# team4-selo-atmega32u4.net
KiCad netlist of a schematic drawn in EAGLE
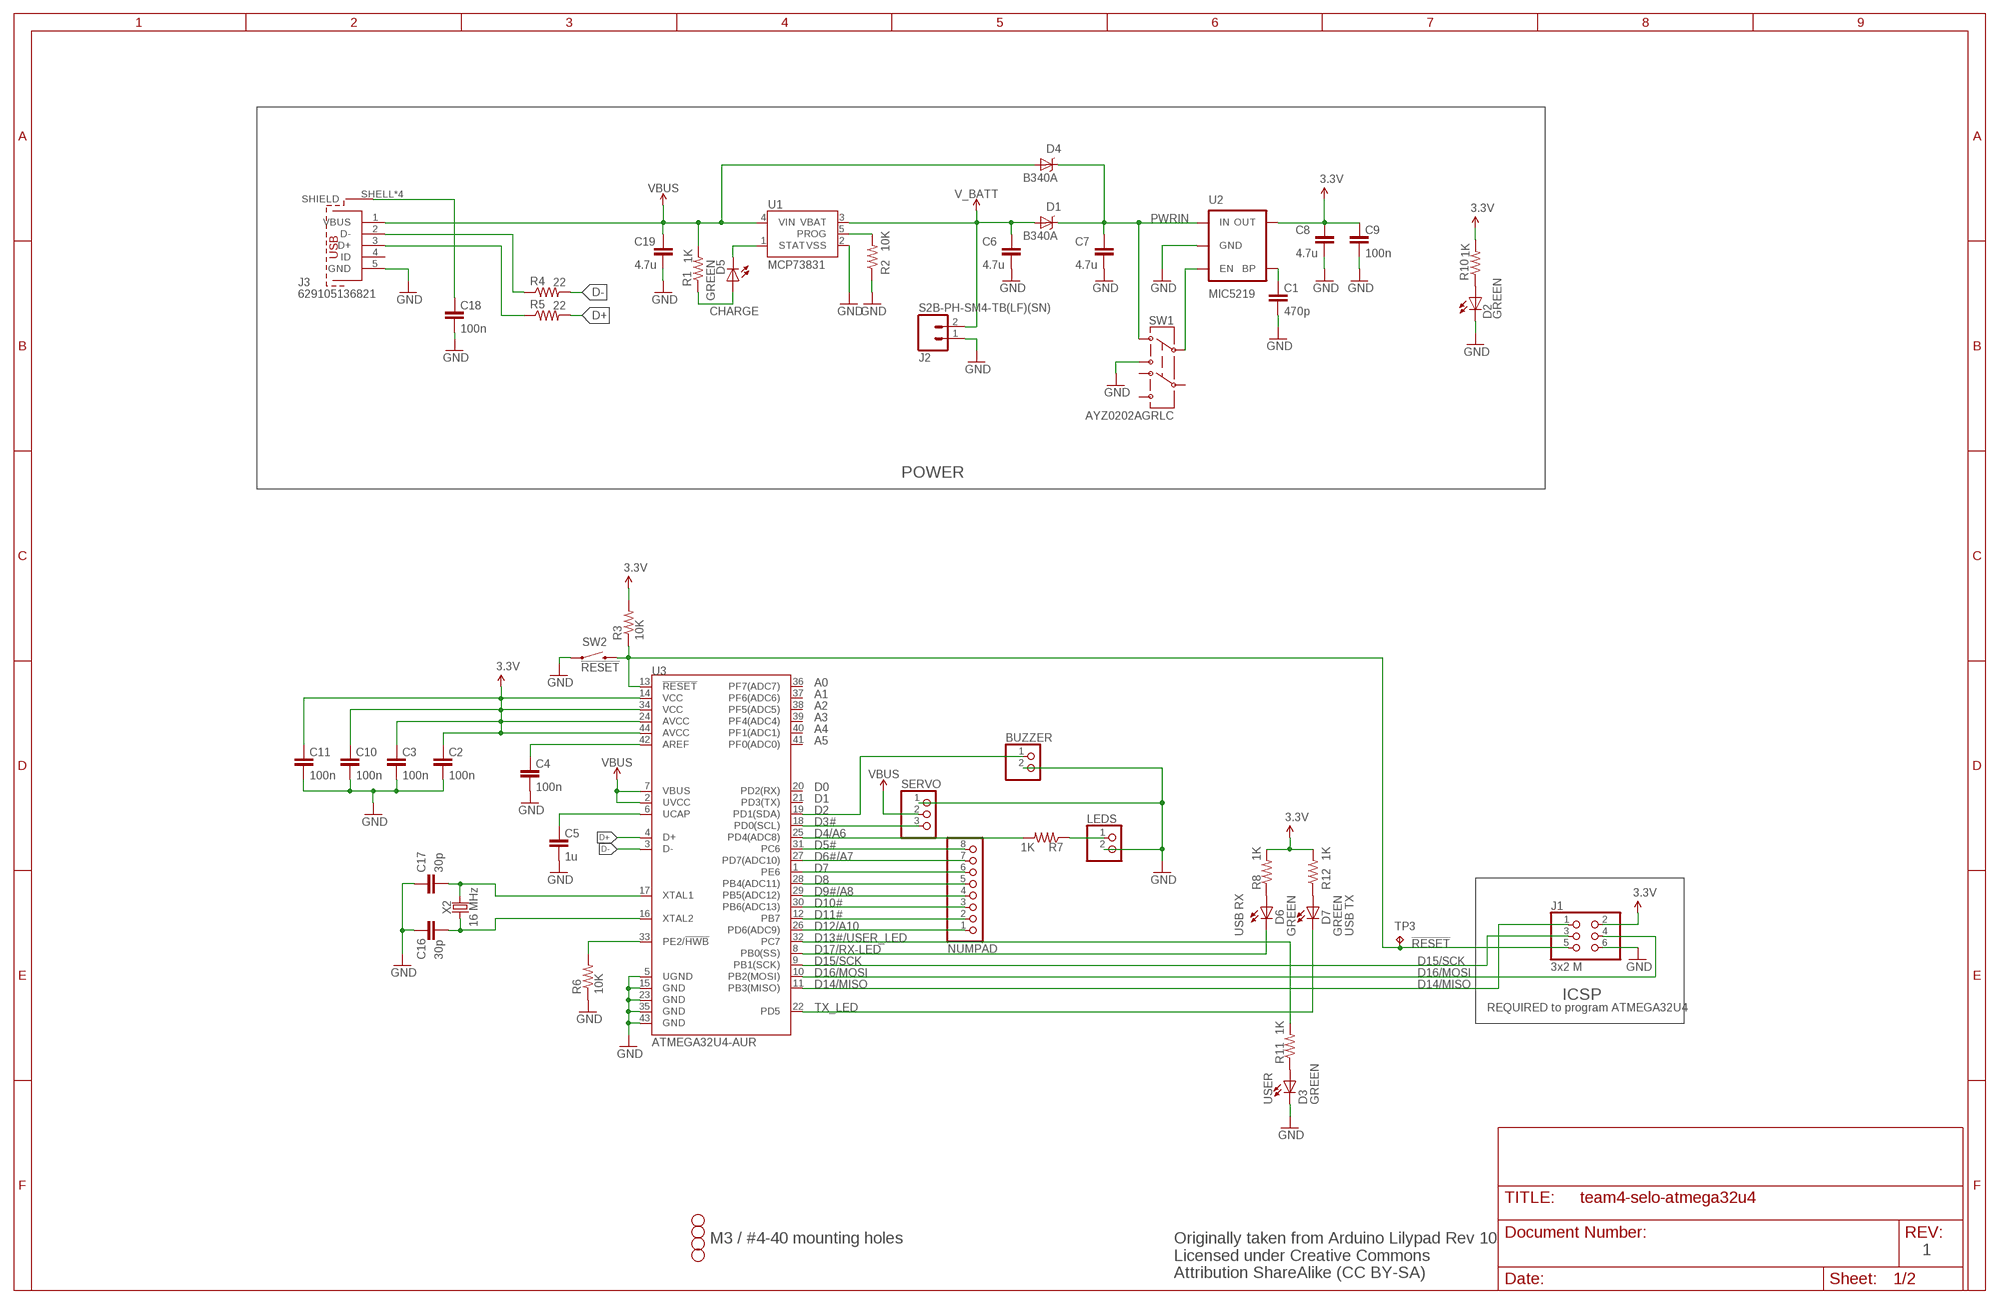
[diagram p0: schematic, sheet 1]

(export (version "E")
  (design (tool "Eeschema 10.0.6"))
  (components
    (comp (ref "BUZZER")
      (value "PINHD-1X2")
      (footprint "eagle-import:1X02")
      (libsource (lib "eagle-import") (part "PINHD-1X2"))
    )
    (comp (ref "C1")
      (value "470p")
      (footprint "eagle-import:C0805K")
      (fields (field (name "MFR") "Samsung") (field (name "MPN") "CL21B471KBANNNC"))
      (libsource (lib "eagle-import") (part "C-EUC0805K"))
    )
    (comp (ref "C2")
      (value "100n")
      (footprint "eagle-import:C0805K")
      (fields (field (name "MFR") "Samsung") (field (name "MPN") "CL21B104KBCNNNC"))
      (libsource (lib "eagle-import") (part "C-EUC0805K"))
    )
    (comp (ref "C3")
      (value "100n")
      (footprint "eagle-import:C0805K")
      (fields (field (name "MFR") "Samsung") (field (name "MPN") "CL21B104KBCNNNC"))
      (libsource (lib "eagle-import") (part "C-EUC0805K"))
    )
    (comp (ref "C4")
      (value "100n")
      (footprint "eagle-import:C0805K")
      (fields (field (name "MFR") "Samsung") (field (name "MPN") "CL21B104KBCNNNC"))
      (libsource (lib "eagle-import") (part "C-EUC0805K"))
    )
    (comp (ref "C5")
      (value "1u")
      (footprint "eagle-import:C0805K")
      (fields (field (name "MFR") "Samsung") (field (name "MPN") "CL21B105KOFNNNG"))
      (libsource (lib "eagle-import") (part "C-EUC0805K"))
    )
    (comp (ref "C6")
      (value "4.7u")
      (footprint "eagle-import:C0805K")
      (fields (field (name "MFR") "Samsung") (field (name "MPN") "CL21A475KOFNNNE"))
      (libsource (lib "eagle-import") (part "C-EUC0805K"))
    )
    (comp (ref "C7")
      (value "4.7u")
      (footprint "eagle-import:C0805K")
      (fields (field (name "MFR") "Samsung") (field (name "MPN") "CL21A475KOFNNNE"))
      (libsource (lib "eagle-import") (part "C-EUC0805K"))
    )
    (comp (ref "C8")
      (value "4.7u")
      (footprint "eagle-import:C0805K")
      (fields (field (name "MFR") "Samsung") (field (name "MPN") "CL21A475KOFNNNE"))
      (libsource (lib "eagle-import") (part "C-EUC0805K"))
    )
    (comp (ref "C9")
      (value "100n")
      (footprint "eagle-import:C0805K")
      (fields (field (name "MFR") "Samsung") (field (name "MPN") "CL21B104KBCNNNC"))
      (libsource (lib "eagle-import") (part "C-EUC0805K"))
    )
    (comp (ref "C10")
      (value "100n")
      (footprint "eagle-import:C0805K")
      (fields (field (name "MFR") "Samsung") (field (name "MPN") "CL21B104KBCNNNC"))
      (libsource (lib "eagle-import") (part "C-EUC0805K"))
    )
    (comp (ref "C11")
      (value "100n")
      (footprint "eagle-import:C0805K")
      (fields (field (name "MFR") "Samsung") (field (name "MPN") "CL21B104KBCNNNC"))
      (libsource (lib "eagle-import") (part "C-EUC0805K"))
    )
    (comp (ref "C16")
      (value "30p")
      (footprint "eagle-import:C0805K")
      (fields (field (name "MFR") "Samsung") (field (name "MPN") "CL21C300JBANNNC"))
      (libsource (lib "eagle-import") (part "C-EUC0805K"))
    )
    (comp (ref "C17")
      (value "30p")
      (footprint "eagle-import:C0805K")
      (fields (field (name "MFR") "Samsung") (field (name "MPN") "CL21C180JBANNNC"))
      (libsource (lib "eagle-import") (part "C-EUC0805K"))
    )
    (comp (ref "C18")
      (value "100n")
      (footprint "eagle-import:C0805K")
      (fields (field (name "MFR") "Samsung") (field (name "MPN") "CL21B104KBCNNNC"))
      (libsource (lib "eagle-import") (part "C-EUC0805K"))
    )
    (comp (ref "C19")
      (value "4.7u")
      (footprint "eagle-import:C0805K")
      (fields (field (name "MFR") "Samsung") (field (name "MPN") "CL21A475KOFNNNE"))
      (libsource (lib "eagle-import") (part "C-EUC0805K"))
    )
    (comp (ref "D1")
      (value "B340A")
      (footprint "eagle-import:SMA-DIODE")
      (fields (field (name "MFR") "Diodes Inc") (field (name "MPN") "B340AE-13"))
      (libsource (lib "eagle-import") (part "DIODE-SCHOTTKY_"))
    )
    (comp (ref "D2")
      (value "GREEN")
      (footprint "eagle-import:CHIP-LED0805")
      (fields (field (name "MFR") "Würth Elektronik") (field (name "MPN") "150080GS75000"))
      (libsource (lib "eagle-import") (part "LEDCHIP-LED0805"))
    )
    (comp (ref "D3")
      (value "GREEN")
      (footprint "eagle-import:CHIP-LED0805")
      (fields (field (name "MFR") "Würth Elektronik") (field (name "MPN") "150080GS75000"))
      (libsource (lib "eagle-import") (part "LEDCHIP-LED0805"))
    )
    (comp (ref "D4")
      (value "B340A")
      (footprint "eagle-import:SMA-DIODE")
      (fields (field (name "MFR") "Diodes Inc") (field (name "MPN") "B340AE-13"))
      (libsource (lib "eagle-import") (part "DIODE-SCHOTTKY_"))
    )
    (comp (ref "D5")
      (value "GREEN")
      (footprint "eagle-import:CHIP-LED0805")
      (fields (field (name "MFR") "Würth Elektronik") (field (name "MPN") "150080GS75000"))
      (libsource (lib "eagle-import") (part "LEDCHIP-LED0805"))
    )
    (comp (ref "D6")
      (value "GREEN")
      (footprint "eagle-import:CHIP-LED0805")
      (fields (field (name "MFR") "Würth Elektronik") (field (name "MPN") "150080GS75000"))
      (libsource (lib "eagle-import") (part "LEDCHIP-LED0805"))
    )
    (comp (ref "D7")
      (value "GREEN")
      (footprint "eagle-import:CHIP-LED0805")
      (fields (field (name "MFR") "Würth Elektronik") (field (name "MPN") "150080GS75000"))
      (libsource (lib "eagle-import") (part "LEDCHIP-LED0805"))
    )
    (comp (ref "H1")
      (value "STAND-OFF")
      (footprint "eagle-import:STAND-OFF")
      (libsource (lib "eagle-import") (part "STAND-OFF"))
    )
    (comp (ref "H2")
      (value "STAND-OFF")
      (footprint "eagle-import:STAND-OFF")
      (libsource (lib "eagle-import") (part "STAND-OFF"))
    )
    (comp (ref "H3")
      (value "STAND-OFF")
      (footprint "eagle-import:STAND-OFF")
      (libsource (lib "eagle-import") (part "STAND-OFF"))
    )
    (comp (ref "H4")
      (value "STAND-OFF")
      (footprint "eagle-import:STAND-OFF")
      (libsource (lib "eagle-import") (part "STAND-OFF"))
    )
    (comp (ref "J1")
      (value "3x2 M")
      (footprint "eagle-import:2X03")
      (fields (field (name "MFR") "Harwin") (field (name "MPN") "M20-9980345"))
      (libsource (lib "eagle-import") (part "PINHD-2X3"))
    )
    (comp (ref "J2")
      (value "S2B-PH-SM4-TB(LF)(SN)")
      (footprint "eagle-import:JST-2-SMD")
      (fields (field (name "MFR") "JST"))
      (libsource (lib "eagle-import") (part "M02-JST-2MM-SMT"))
    )
    (comp (ref "J3")
      (value "629105136821")
      (footprint "eagle-import:629105136821")
      (fields (field (name "MFR") "Wurth"))
      (libsource (lib "eagle-import") (part "629105136821"))
    )
    (comp (ref "LEDS")
      (value "PINHD-1X2")
      (footprint "eagle-import:1X02")
      (libsource (lib "eagle-import") (part "PINHD-1X2"))
    )
    (comp (ref "NUMPAD")
      (value "PINHD-1X8")
      (footprint "eagle-import:1X08")
      (libsource (lib "eagle-import") (part "PINHD-1X8"))
    )
    (comp (ref "R1")
      (value "1K")
      (footprint "eagle-import:R0805")
      (fields (field (name "MFR") "Yageo") (field (name "MPN") "RC0805FR-071KL"))
      (libsource (lib "eagle-import") (part "R-US_R0805"))
    )
    (comp (ref "R2")
      (value "10K")
      (footprint "eagle-import:R0805")
      (fields (field (name "MFR") "Yageo") (field (name "MPN") "RC0805FR-0710KL"))
      (libsource (lib "eagle-import") (part "R-US_R0805"))
    )
    (comp (ref "R3")
      (value "10K")
      (footprint "eagle-import:R0805")
      (fields (field (name "MFR") "Yageo") (field (name "MPN") "RC0805FR-0710KL"))
      (libsource (lib "eagle-import") (part "R-US_R0805"))
    )
    (comp (ref "R4")
      (value "22")
      (footprint "eagle-import:R0805")
      (fields (field (name "MFR") "Yageo") (field (name "MPN") "RC0805FR-0722RL"))
      (libsource (lib "eagle-import") (part "R-US_R0805"))
    )
    (comp (ref "R5")
      (value "22")
      (footprint "eagle-import:R0805")
      (fields (field (name "MFR") "Yageo") (field (name "MPN") "RC0805FR-0722RL"))
      (libsource (lib "eagle-import") (part "R-US_R0805"))
    )
    (comp (ref "R6")
      (value "10K")
      (footprint "eagle-import:R0805")
      (fields (field (name "MFR") "Yageo") (field (name "MPN") "RC0805FR-0710KL"))
      (libsource (lib "eagle-import") (part "R-US_R0805"))
    )
    (comp (ref "R7")
      (value "1K")
      (footprint "eagle-import:R0805")
      (fields (field (name "MFR") "Yageo") (field (name "MPN") "RC0805FR-071KL"))
      (libsource (lib "eagle-import") (part "R-US_R0805"))
    )
    (comp (ref "R8")
      (value "1K")
      (footprint "eagle-import:R0805")
      (fields (field (name "MFR") "Yageo") (field (name "MPN") "RC0805FR-071KL"))
      (libsource (lib "eagle-import") (part "R-US_R0805"))
    )
    (comp (ref "R10")
      (value "1K")
      (footprint "eagle-import:R0805")
      (fields (field (name "MFR") "Yageo") (field (name "MPN") "RC0805FR-071KL"))
      (libsource (lib "eagle-import") (part "R-US_R0805"))
    )
    (comp (ref "R11")
      (value "1K")
      (footprint "eagle-import:R0805")
      (fields (field (name "MFR") "Yageo") (field (name "MPN") "RC0805FR-071KL"))
      (libsource (lib "eagle-import") (part "R-US_R0805"))
    )
    (comp (ref "R12")
      (value "1K")
      (footprint "eagle-import:R0805")
      (fields (field (name "MFR") "Yageo") (field (name "MPN") "RC0805FR-071KL"))
      (libsource (lib "eagle-import") (part "R-US_R0805"))
    )
    (comp (ref "SERVO")
      (value "PINHD-1X3")
      (footprint "eagle-import:1X03")
      (libsource (lib "eagle-import") (part "PINHD-1X3"))
    )
    (comp (ref "SW1")
      (value "AYZ0202AGRLC")
      (footprint "eagle-import:AYZ0202")
      (fields (field (name "MFR") "C&K"))
      (libsource (lib "eagle-import") (part "SWITCH-DPDTSMD"))
    )
    (comp (ref "SW2")
      (value "!RESET")
      (footprint "eagle-import:TACTILE_SWITCH_SMD")
      (fields (field (name "MFR") "C&K") (field (name "MPN") "RS-187R05A2-DS MT RT"))
      (libsource (lib "eagle-import") (part "SWITCH-MOMENTARY-2SMD"))
    )
    (comp (ref "TP3")
      (value "TPPAD1-13")
      (footprint "eagle-import:P1-13")
      (libsource (lib "eagle-import") (part "TPPAD1-13"))
    )
    (comp (ref "U1")
      (value "MCP73831")
      (footprint "eagle-import:SOT23-5")
      (fields (field (name "MFR") "Microchip") (field (name "MPN") "MCP73831T-2ACI/OT"))
      (libsource (lib "eagle-import") (part "MCP73831"))
    )
    (comp (ref "U2")
      (value "MIC5219")
      (footprint "eagle-import:SOT23-5")
      (fields (field (name "MFR") "Microchip") (field (name "MPN") "MIC5219-3.3YM5-TR"))
      (libsource (lib "eagle-import") (part "V_REG_MIC5219SMD"))
    )
    (comp (ref "U3")
      (value "ATMEGA32U4-AUR")
      (footprint "eagle-import:TQFP44")
      (fields (field (name "MFR") "Microchip") (field (name "PROD_ID") "IC-10828"))
      (libsource (lib "eagle-import") (part "ATMEGA32U4TQFP-44"))
    )
    (comp (ref "X2")
      (value "16 MHz")
      (footprint "eagle-import:HC49UP")
      (fields (field (name "MFR") "ECS") (field (name "MPN") "ECS-160-18-5PX-TR"))
      (libsource (lib "eagle-import") (part "CRYSTALSMD-HC49UP"))
    )
  )
  (nets
    (net (code "1") (name "3.3V") (class "Default")
      (node (ref "C10") (pin "1") (pinfunction "1_1") (pintype "passive"))
      (node (ref "C11") (pin "1") (pinfunction "1_1") (pintype "passive"))
      (node (ref "C2") (pin "1") (pinfunction "1_1") (pintype "passive"))
      (node (ref "C3") (pin "1") (pinfunction "1_1") (pintype "passive"))
      (node (ref "C8") (pin "1") (pinfunction "1_1") (pintype "passive"))
      (node (ref "C9") (pin "1") (pinfunction "1_1") (pintype "passive"))
      (node (ref "J1") (pin "2") (pinfunction "2_2") (pintype "passive"))
      (node (ref "R10") (pin "2") (pinfunction "2_2") (pintype "passive"))
      (node (ref "R12") (pin "2") (pinfunction "2_2") (pintype "passive"))
      (node (ref "R3") (pin "2") (pinfunction "2_2") (pintype "passive"))
      (node (ref "R8") (pin "2") (pinfunction "2_2") (pintype "passive"))
      (node (ref "U2") (pin "5") (pinfunction "OUT_5") (pintype "passive"))
      (node (ref "U3") (pin "14") (pinfunction "VCC_14") (pintype "bidirectional"))
      (node (ref "U3") (pin "24") (pinfunction "AVCC_24") (pintype "bidirectional"))
      (node (ref "U3") (pin "34") (pinfunction "VCC_34") (pintype "bidirectional"))
      (node (ref "U3") (pin "44") (pinfunction "AVCC_44") (pintype "bidirectional"))
    )
    (net (code "2") (name "D+") (class "Default")
      (node (ref "R5") (pin "2") (pinfunction "2_2") (pintype "passive"))
      (node (ref "U3") (pin "4") (pinfunction "D+_4") (pintype "bidirectional"))
    )
    (net (code "3") (name "D-") (class "Default")
      (node (ref "R4") (pin "2") (pinfunction "2_2") (pintype "passive"))
      (node (ref "U3") (pin "3") (pinfunction "D-_3") (pintype "bidirectional"))
    )
    (net (code "4") (name "D13#{slash}USER_LED") (class "Default")
      (node (ref "R11") (pin "2") (pinfunction "2_2") (pintype "passive"))
      (node (ref "U3") (pin "32") (pinfunction "PC7_32") (pintype "bidirectional"))
    )
    (net (code "5") (name "D14{slash}MISO") (class "Default")
      (node (ref "J1") (pin "1") (pinfunction "1_1") (pintype "passive"))
      (node (ref "U3") (pin "11") (pinfunction "PB3(MISO)_11") (pintype "bidirectional"))
    )
    (net (code "6") (name "D15{slash}SCK") (class "Default")
      (node (ref "J1") (pin "3") (pinfunction "3_3") (pintype "passive"))
      (node (ref "U3") (pin "9") (pinfunction "PB1(SCK)_9") (pintype "bidirectional"))
    )
    (net (code "7") (name "D16{slash}MOSI") (class "Default")
      (node (ref "J1") (pin "4") (pinfunction "4_4") (pintype "passive"))
      (node (ref "U3") (pin "10") (pinfunction "PB2(MOSI)_10") (pintype "bidirectional"))
    )
    (net (code "8") (name "D17{slash}RX-LED") (class "Default")
      (node (ref "D6") (pin "C") (pinfunction "C_C") (pintype "passive"))
      (node (ref "U3") (pin "8") (pinfunction "PB0(SS)_8") (pintype "bidirectional"))
    )
    (net (code "9") (name "GND") (class "Default")
      (node (ref "BUZZER") (pin "2") (pinfunction "2_2") (pintype "passive"))
      (node (ref "C1") (pin "2") (pinfunction "2_2") (pintype "passive"))
      (node (ref "C10") (pin "2") (pinfunction "2_2") (pintype "passive"))
      (node (ref "C11") (pin "2") (pinfunction "2_2") (pintype "passive"))
      (node (ref "C16") (pin "2") (pinfunction "2_2") (pintype "passive"))
      (node (ref "C17") (pin "2") (pinfunction "2_2") (pintype "passive"))
      (node (ref "C18") (pin "2") (pinfunction "2_2") (pintype "passive"))
      (node (ref "C19") (pin "2") (pinfunction "2_2") (pintype "passive"))
      (node (ref "C2") (pin "2") (pinfunction "2_2") (pintype "passive"))
      (node (ref "C3") (pin "2") (pinfunction "2_2") (pintype "passive"))
      (node (ref "C4") (pin "2") (pinfunction "2_2") (pintype "passive"))
      (node (ref "C5") (pin "2") (pinfunction "2_2") (pintype "passive"))
      (node (ref "C6") (pin "2") (pinfunction "2_2") (pintype "passive"))
      (node (ref "C7") (pin "2") (pinfunction "2_2") (pintype "passive"))
      (node (ref "C8") (pin "2") (pinfunction "2_2") (pintype "passive"))
      (node (ref "C9") (pin "2") (pinfunction "2_2") (pintype "passive"))
      (node (ref "D2") (pin "C") (pinfunction "C_C") (pintype "passive"))
      (node (ref "D3") (pin "C") (pinfunction "C_C") (pintype "passive"))
      (node (ref "J1") (pin "6") (pinfunction "6_6") (pintype "passive"))
      (node (ref "J2") (pin "1") (pinfunction "2_1") (pintype "passive"))
      (node (ref "J3") (pin "5") (pinfunction "GND_5") (pintype "passive"))
      (node (ref "LEDS") (pin "2") (pinfunction "2_2") (pintype "passive"))
      (node (ref "R2") (pin "1") (pinfunction "1_1") (pintype "passive"))
      (node (ref "R6") (pin "1") (pinfunction "1_1") (pintype "passive"))
      (node (ref "SERVO") (pin "1") (pinfunction "1_1") (pintype "passive"))
      (node (ref "SW1") (pin "3") (pinfunction "3_3") (pintype "bidirectional"))
      (node (ref "SW2") (pin "1") (pinfunction "1_1") (pintype "passive"))
      (node (ref "U1") (pin "2") (pinfunction "VSS_2") (pintype "power_in"))
      (node (ref "U2") (pin "2") (pinfunction "GND_2") (pintype "input"))
      (node (ref "U3") (pin "15") (pinfunction "GND_15") (pintype "bidirectional"))
      (node (ref "U3") (pin "23") (pinfunction "GND_23") (pintype "bidirectional"))
      (node (ref "U3") (pin "35") (pinfunction "GND_35") (pintype "bidirectional"))
      (node (ref "U3") (pin "43") (pinfunction "GND_43") (pintype "bidirectional"))
      (node (ref "U3") (pin "5") (pinfunction "UGND_5") (pintype "bidirectional"))
    )
    (net (code "10") (name "Net-(C18-Pad1)") (class "Default")
      (node (ref "C18") (pin "1") (pinfunction "1_1") (pintype "passive"))
      (node (ref "J3") (pin "SHELL") (pinfunction "SHIELD_SHELL") (pintype "passive"))
      (node (ref "J3") (pin "SHELL1") (pinfunction "SHIELD_SHELL1") (pintype "passive"))
      (node (ref "J3") (pin "SHELL2") (pinfunction "SHIELD_SHELL2") (pintype "passive"))
      (node (ref "J3") (pin "SHELL3") (pinfunction "SHIELD_SHELL3") (pintype "passive"))
    )
    (net (code "11") (name "Net-(D2-PadA)") (class "Default")
      (node (ref "D2") (pin "A") (pinfunction "A_A") (pintype "passive"))
      (node (ref "R10") (pin "1") (pinfunction "1_1") (pintype "passive"))
    )
    (net (code "12") (name "Net-(D3-PadA)") (class "Default")
      (node (ref "D3") (pin "A") (pinfunction "A_A") (pintype "passive"))
      (node (ref "R11") (pin "1") (pinfunction "1_1") (pintype "passive"))
    )
    (net (code "13") (name "Net-(D5-PadA)") (class "Default")
      (node (ref "D5") (pin "A") (pinfunction "A_A") (pintype "passive"))
      (node (ref "R1") (pin "1") (pinfunction "1_1") (pintype "passive"))
    )
    (net (code "14") (name "Net-(D6-PadA)") (class "Default")
      (node (ref "D6") (pin "A") (pinfunction "A_A") (pintype "passive"))
      (node (ref "R8") (pin "1") (pinfunction "1_1") (pintype "passive"))
    )
    (net (code "15") (name "Net-(D7-PadA)") (class "Default")
      (node (ref "D7") (pin "A") (pinfunction "A_A") (pintype "passive"))
      (node (ref "R12") (pin "1") (pinfunction "1_1") (pintype "passive"))
    )
    (net (code "16") (name "Net-(J3-D+)") (class "Default")
      (node (ref "J3") (pin "3") (pinfunction "D+_3") (pintype "passive"))
      (node (ref "R5") (pin "1") (pinfunction "1_1") (pintype "passive"))
    )
    (net (code "17") (name "Net-(J3-D-)") (class "Default")
      (node (ref "J3") (pin "2") (pinfunction "D-_2") (pintype "passive"))
      (node (ref "R4") (pin "1") (pinfunction "1_1") (pintype "passive"))
    )
    (net (code "18") (name "Net-(LEDS-Pad1)") (class "Default")
      (node (ref "LEDS") (pin "1") (pinfunction "1_1") (pintype "passive"))
      (node (ref "R7") (pin "1") (pinfunction "1_1") (pintype "passive"))
    )
    (net (code "19") (name "Net-(U1-PROG)") (class "Default")
      (node (ref "R2") (pin "2") (pinfunction "2_2") (pintype "passive"))
      (node (ref "U1") (pin "5") (pinfunction "PROG_5") (pintype "input"))
    )
    (net (code "20") (name "Net-(U1-STAT)") (class "Default")
      (node (ref "D5") (pin "C") (pinfunction "C_C") (pintype "passive"))
      (node (ref "U1") (pin "1") (pinfunction "STAT_1") (pintype "output"))
    )
    (net (code "21") (name "Net-(U2-BP)") (class "Default")
      (node (ref "C1") (pin "1") (pinfunction "1_1") (pintype "passive"))
      (node (ref "U2") (pin "4") (pinfunction "BP_4") (pintype "input"))
    )
    (net (code "22") (name "Net-(U2-EN)") (class "Default")
      (node (ref "SW1") (pin "2") (pinfunction "2_2") (pintype "bidirectional"))
      (node (ref "U2") (pin "3") (pinfunction "EN_3") (pintype "input"))
    )
    (net (code "23") (name "Net-(U3-AREF)") (class "Default")
      (node (ref "C4") (pin "1") (pinfunction "1_1") (pintype "passive"))
      (node (ref "U3") (pin "42") (pinfunction "AREF_42") (pintype "bidirectional"))
    )
    (net (code "24") (name "Net-(U3-PB4(ADC11))") (class "Default")
      (node (ref "NUMPAD") (pin "5") (pinfunction "5_5") (pintype "passive"))
      (node (ref "U3") (pin "28") (pinfunction "PB4(ADC11)_28") (pintype "bidirectional"))
    )
    (net (code "25") (name "Net-(U3-PB5(ADC12))") (class "Default")
      (node (ref "NUMPAD") (pin "4") (pinfunction "4_4") (pintype "passive"))
      (node (ref "U3") (pin "29") (pinfunction "PB5(ADC12)_29") (pintype "bidirectional"))
    )
    (net (code "26") (name "Net-(U3-PB6(ADC13))") (class "Default")
      (node (ref "NUMPAD") (pin "3") (pinfunction "3_3") (pintype "passive"))
      (node (ref "U3") (pin "30") (pinfunction "PB6(ADC13)_30") (pintype "bidirectional"))
    )
    (net (code "27") (name "Net-(U3-PB7)") (class "Default")
      (node (ref "NUMPAD") (pin "2") (pinfunction "2_2") (pintype "passive"))
      (node (ref "U3") (pin "12") (pinfunction "PB7_12") (pintype "bidirectional"))
    )
    (net (code "28") (name "Net-(U3-PC6)") (class "Default")
      (node (ref "NUMPAD") (pin "8") (pinfunction "8_8") (pintype "passive"))
      (node (ref "U3") (pin "31") (pinfunction "PC6_31") (pintype "bidirectional"))
    )
    (net (code "29") (name "Net-(U3-PD0(SCL))") (class "Default")
      (node (ref "SERVO") (pin "3") (pinfunction "3_3") (pintype "passive"))
      (node (ref "U3") (pin "18") (pinfunction "PD0(SCL)_18") (pintype "bidirectional"))
    )
    (net (code "30") (name "Net-(U3-PD1(SDA))") (class "Default")
      (node (ref "BUZZER") (pin "1") (pinfunction "1_1") (pintype "passive"))
      (node (ref "U3") (pin "19") (pinfunction "PD1(SDA)_19") (pintype "bidirectional"))
    )
    (net (code "31") (name "Net-(U3-PD4(ADC8))") (class "Default")
      (node (ref "R7") (pin "2") (pinfunction "2_2") (pintype "passive"))
      (node (ref "U3") (pin "25") (pinfunction "PD4(ADC8)_25") (pintype "bidirectional"))
    )
    (net (code "32") (name "Net-(U3-PD6(ADC9))") (class "Default")
      (node (ref "NUMPAD") (pin "1") (pinfunction "1_1") (pintype "passive"))
      (node (ref "U3") (pin "26") (pinfunction "PD6(ADC9)_26") (pintype "bidirectional"))
    )
    (net (code "33") (name "Net-(U3-PD7(ADC10))") (class "Default")
      (node (ref "NUMPAD") (pin "7") (pinfunction "7_7") (pintype "passive"))
      (node (ref "U3") (pin "27") (pinfunction "PD7(ADC10)_27") (pintype "bidirectional"))
    )
    (net (code "34") (name "Net-(U3-PE2{slash}~{HWB})") (class "Default")
      (node (ref "R6") (pin "2") (pinfunction "2_2") (pintype "passive"))
      (node (ref "U3") (pin "33") (pinfunction "PE2/~{HWB}_33") (pintype "bidirectional"))
    )
    (net (code "35") (name "Net-(U3-PE6)") (class "Default")
      (node (ref "NUMPAD") (pin "6") (pinfunction "6_6") (pintype "passive"))
      (node (ref "U3") (pin "1") (pinfunction "PE6_1") (pintype "bidirectional"))
    )
    (net (code "36") (name "Net-(U3-UCAP)") (class "Default")
      (node (ref "C5") (pin "1") (pinfunction "1_1") (pintype "passive"))
      (node (ref "U3") (pin "6") (pinfunction "UCAP_6") (pintype "bidirectional"))
    )
    (net (code "37") (name "Net-(U3-XTAL1)") (class "Default")
      (node (ref "C17") (pin "1") (pinfunction "1_1") (pintype "passive"))
      (node (ref "U3") (pin "17") (pinfunction "XTAL1_17") (pintype "bidirectional"))
      (node (ref "X2") (pin "2") (pinfunction "2_2") (pintype "passive"))
    )
    (net (code "38") (name "Net-(U3-XTAL2)") (class "Default")
      (node (ref "C16") (pin "1") (pinfunction "1_1") (pintype "passive"))
      (node (ref "U3") (pin "16") (pinfunction "XTAL2_16") (pintype "bidirectional"))
      (node (ref "X2") (pin "1") (pinfunction "1_1") (pintype "passive"))
    )
    (net (code "39") (name "PWRIN") (class "Default")
      (node (ref "C7") (pin "1") (pinfunction "1_1") (pintype "passive"))
      (node (ref "D1") (pin "C") (pinfunction "C_C") (pintype "passive"))
      (node (ref "D4") (pin "C") (pinfunction "C_C") (pintype "passive"))
      (node (ref "SW1") (pin "1") (pinfunction "1_1") (pintype "bidirectional"))
      (node (ref "U2") (pin "1") (pinfunction "IN_1") (pintype "input"))
    )
    (net (code "40") (name "TX_LED") (class "Default")
      (node (ref "D7") (pin "C") (pinfunction "C_C") (pintype "passive"))
      (node (ref "U3") (pin "22") (pinfunction "PD5_22") (pintype "bidirectional"))
    )
    (net (code "41") (name "VBUS") (class "Default")
      (node (ref "C19") (pin "1") (pinfunction "1_1") (pintype "passive"))
      (node (ref "D4") (pin "A") (pinfunction "A_A") (pintype "passive"))
      (node (ref "J3") (pin "1") (pinfunction "VBUS_1") (pintype "passive"))
      (node (ref "R1") (pin "2") (pinfunction "2_2") (pintype "passive"))
      (node (ref "SERVO") (pin "2") (pinfunction "2_2") (pintype "passive"))
      (node (ref "U1") (pin "4") (pinfunction "VIN_4") (pintype "power_in"))
      (node (ref "U3") (pin "2") (pinfunction "UVCC_2") (pintype "bidirectional"))
      (node (ref "U3") (pin "7") (pinfunction "VBUS_7") (pintype "bidirectional"))
    )
    (net (code "42") (name "V_BATT") (class "Default")
      (node (ref "C6") (pin "1") (pinfunction "1_1") (pintype "passive"))
      (node (ref "D1") (pin "A") (pinfunction "A_A") (pintype "passive"))
      (node (ref "J2") (pin "2") (pinfunction "1_2") (pintype "passive"))
      (node (ref "U1") (pin "3") (pinfunction "VBAT_3") (pintype "power_in"))
    )
    (net (code "43") (name "unconnected-(J3-ID-Pad4)") (class "Default")
      (node (ref "J3") (pin "4") (pinfunction "ID_4") (pintype "passive"))
    )
    (net (code "44") (name "unconnected-(SW1-Pad4)") (class "Default")
      (node (ref "SW1") (pin "4") (pinfunction "4_4") (pintype "bidirectional"))
    )
    (net (code "45") (name "unconnected-(SW1-Pad5)") (class "Default")
      (node (ref "SW1") (pin "5") (pinfunction "5_5") (pintype "bidirectional"))
    )
    (net (code "46") (name "unconnected-(SW1-Pad6)") (class "Default")
      (node (ref "SW1") (pin "6") (pinfunction "6_6") (pintype "bidirectional"))
    )
    (net (code "47") (name "unconnected-(U3-PD2(RX)-Pad20)") (class "Default")
      (node (ref "U3") (pin "20") (pinfunction "PD2(RX)_20") (pintype "bidirectional"))
    )
    (net (code "48") (name "unconnected-(U3-PD3(TX)-Pad21)") (class "Default")
      (node (ref "U3") (pin "21") (pinfunction "PD3(TX)_21") (pintype "bidirectional"))
    )
    (net (code "49") (name "unconnected-(U3-PF0(ADC0)-Pad41)") (class "Default")
      (node (ref "U3") (pin "41") (pinfunction "PF0(ADC0)_41") (pintype "bidirectional"))
    )
    (net (code "50") (name "unconnected-(U3-PF1(ADC1)-Pad40)") (class "Default")
      (node (ref "U3") (pin "40") (pinfunction "PF1(ADC1)_40") (pintype "bidirectional"))
    )
    (net (code "51") (name "unconnected-(U3-PF4(ADC4)-Pad39)") (class "Default")
      (node (ref "U3") (pin "39") (pinfunction "PF4(ADC4)_39") (pintype "bidirectional"))
    )
    (net (code "52") (name "unconnected-(U3-PF5(ADC5)-Pad38)") (class "Default")
      (node (ref "U3") (pin "38") (pinfunction "PF5(ADC5)_38") (pintype "bidirectional"))
    )
    (net (code "53") (name "unconnected-(U3-PF6(ADC6)-Pad37)") (class "Default")
      (node (ref "U3") (pin "37") (pinfunction "PF6(ADC6)_37") (pintype "bidirectional"))
    )
    (net (code "54") (name "unconnected-(U3-PF7(ADC7)-Pad36)") (class "Default")
      (node (ref "U3") (pin "36") (pinfunction "PF7(ADC7)_36") (pintype "bidirectional"))
    )
    (net (code "55") (name "~{RESET}") (class "Default")
      (node (ref "J1") (pin "5") (pinfunction "5_5") (pintype "passive"))
      (node (ref "R3") (pin "1") (pinfunction "1_1") (pintype "passive"))
      (node (ref "SW2") (pin "3") (pinfunction "2_3") (pintype "passive"))
      (node (ref "TP3") (pin "TP") (pinfunction "TP_TP") (pintype "input"))
      (node (ref "U3") (pin "13") (pinfunction "~{RESET}_13") (pintype "bidirectional"))
    )
  )
)
